# STM32F103RCT6MinSys.net
KiCad netlist of a schematic drawn in Altium Designer
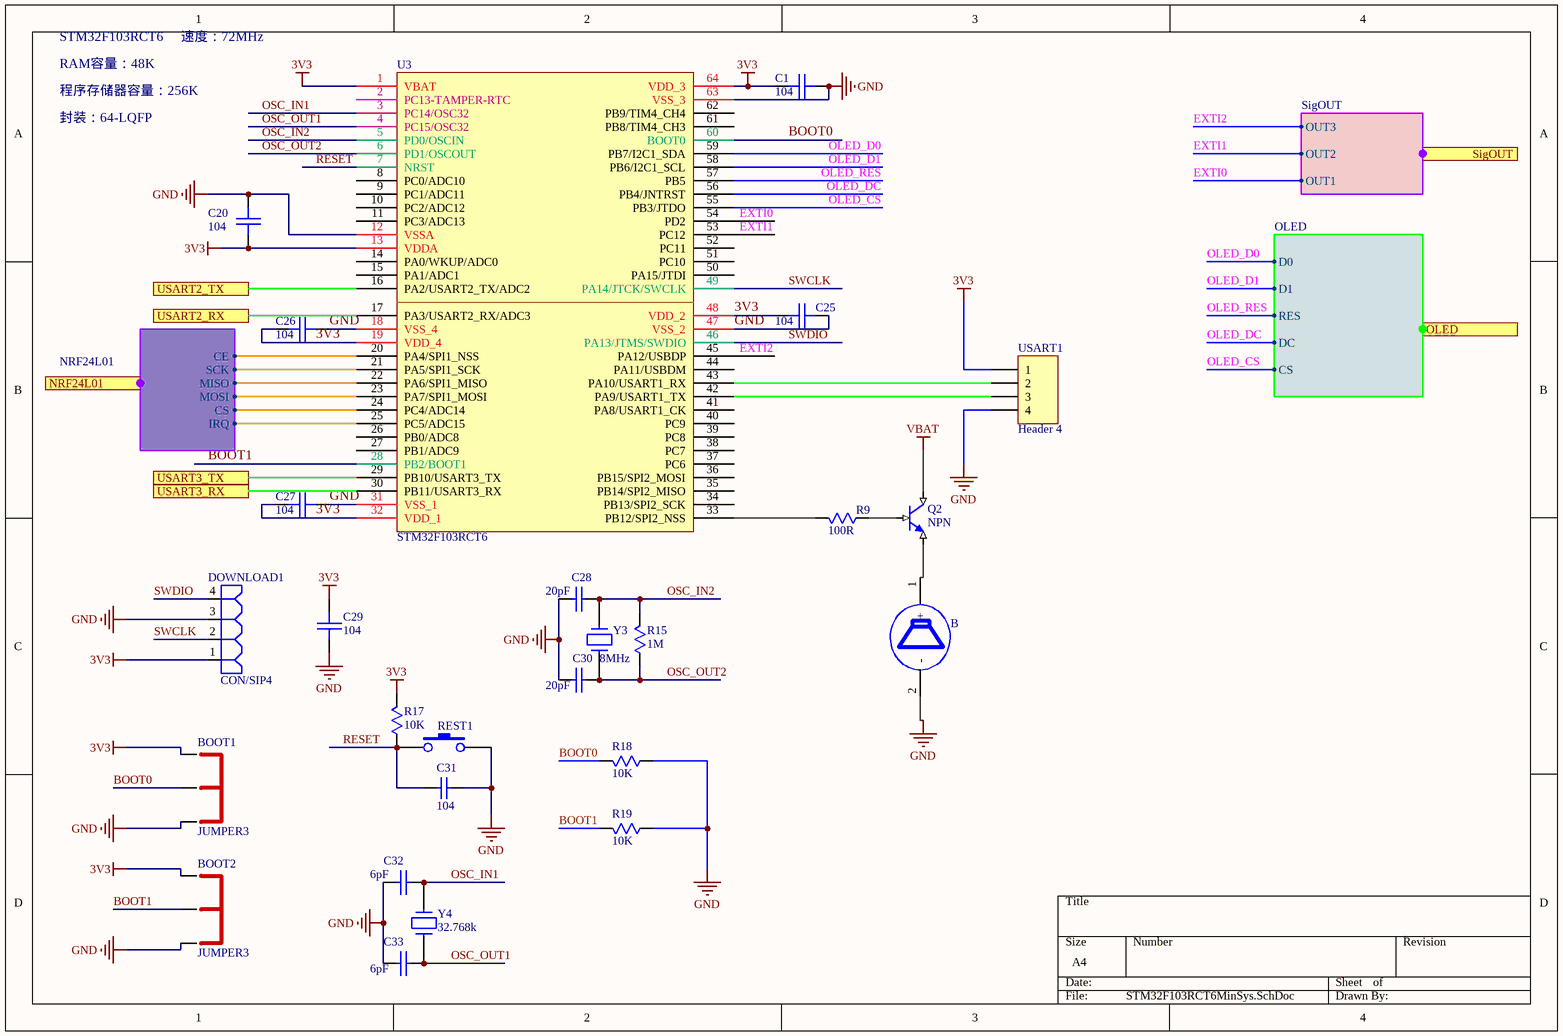
[diagram p0: STM32F103RCT6MinSys.SchDoc]

(export (version "E")
  (design (tool "Eeschema 10.0.6"))
  (components
    (comp (ref "B") (value "BEEP") (footprint "BEEP") (libsource (lib "常用原件库") (part "蜂鸣器")))
    (comp (ref "BOOT1")
      (value "JUMPER3")
      (footprint "Jumper3")
      (description "Jumper")
      (libsource (lib "LQ_Integrated_Library") (part "JUMPER3"))
    )
    (comp (ref "BOOT2")
      (value "JUMPER3")
      (footprint "Jumper3")
      (description "Jumper")
      (libsource (lib "LQ_Integrated_Library") (part "JUMPER3"))
    )
    (comp (ref "C1") (value "104") (footprint "C0603") (libsource (lib "YT1_SCH_99SE") (part "CAP")))
    (comp (ref "C20") (value "104") (footprint "C0603") (libsource (lib "YT1_SCH_99SE") (part "CAP")))
    (comp (ref "C25") (value "104") (footprint "C0603") (libsource (lib "YT1_SCH_99SE") (part "CAP")))
    (comp (ref "C26") (value "104") (footprint "C0603") (libsource (lib "YT1_SCH_99SE") (part "CAP")))
    (comp (ref "C27") (value "104") (footprint "C0603") (libsource (lib "YT1_SCH_99SE") (part "CAP")))
    (comp (ref "C28")
      (value "20pF")
      (footprint "LC-0603_C")
      (description "CAP CHIP 20P 50V(+-5% C0G 0603)")
      (libsource (lib "Miscellaneous Devices") (part "CAP"))
    )
    (comp (ref "C29") (value "104") (footprint "C0603") (libsource (lib "YT1_SCH_99SE") (part "CAP")))
    (comp (ref "C30")
      (value "20pF")
      (footprint "LC-0603_C")
      (description "CAP CHIP 20P 50V(+-5% C0G 0603)")
      (libsource (lib "Miscellaneous Devices") (part "CAP"))
    )
    (comp (ref "C31")
      (value "104")
      (footprint "LC-0603_C")
      (description "GRM39 X7R102K50PT")
      (fields (field (name "PUBLISHER") "Altium Limited"))
      (libsource (lib "") (part "CAP_1"))
    )
    (comp (ref "C32")
      (value "6pF")
      (footprint "LC-0603_C")
      (description "CAP CHIP 20P 50V(+-5% C0G 0603)")
      (libsource (lib "Miscellaneous Devices") (part "CAP"))
    )
    (comp (ref "C33")
      (value "6pF")
      (footprint "LC-0603_C")
      (description "CAP CHIP 20P 50V(+-5% C0G 0603)")
      (libsource (lib "Miscellaneous Devices") (part "CAP"))
    )
    (comp (ref "DOWNLOAD1")
      (value "CON/SIP4")
      (footprint "HDR1X4")
      (libsource (lib "LQ_Integrated_Library") (part "CON/SIP4"))
    )
    (comp (ref "Q2")
      (value "NPN")
      (footprint "SOT23-3")
      (description "triode")
      (libsource (lib "LQ_Integrated_Library") (part "NPN"))
    )
    (comp (ref "R9") (value "100R") (footprint "R0603") (libsource (lib "YT1_SCH_99SE") (part "RES")))
    (comp (ref "R15") (value "1M") (footprint "LC-0603_R") (libsource (lib "YT1_SCH_99SE") (part "RES")))
    (comp (ref "R17") (value "10K") (footprint "R0603") (libsource (lib "YT1_SCH_99SE") (part "RES")))
    (comp (ref "R18") (value "10K") (footprint "R0603") (libsource (lib "YT1_SCH_99SE") (part "RES")))
    (comp (ref "R19") (value "10K") (footprint "R0603") (libsource (lib "YT1_SCH_99SE") (part "RES")))
    (comp (ref "REST1") (value "~") (footprint "KEY-K2") (libsource (lib "*") (part "SW-PB")))
    (comp (ref "U3")
      (value "STM32F103RCT6")
      (footprint "LC-LQFP-64_10x10x05P")
      (libsource (lib "YT1_SCH_99SE") (part "STM32F103RBT6"))
    )
    (comp (ref "USART1")
      (value "Header 4")
      (footprint "HDR1X4")
      (description "Header, 4-Pin")
      (fields (field (name "PUBLISHER") "Altium Limited"))
      (libsource (lib "Miscellaneous Connectors") (part "Header 4"))
    )
    (comp (ref "Y3")
      (value "8MHz")
      (footprint "XTAL-49/S_N")
      (description "Crystal 8MHz PLUG")
      (libsource (lib "*") (part "CRYSTAL"))
    )
    (comp (ref "Y4")
      (value "32.768k")
      (footprint "XTAL_2X6 卧式")
      (description "Crystal 8MHz PLUG")
      (libsource (lib "*") (part "CRYSTAL"))
    )
  )
  (nets
    (net (code "4") (name "/BOOT0") (class "Default")
      (node (ref "BOOT1") (pin "2") (pinfunction "2_2") (pintype "passive"))
      (node (ref "R18") (pin "2") (pinfunction "2_2") (pintype "passive"))
      (node (ref "U3") (pin "60") (pinfunction "BOOT0_60") (pintype "passive"))
    )
    (net (code "5") (name "/BOOT1") (class "Default")
      (node (ref "BOOT2") (pin "2") (pinfunction "2_2") (pintype "passive"))
      (node (ref "R19") (pin "2") (pinfunction "2_2") (pintype "passive"))
      (node (ref "U3") (pin "28") (pinfunction "PB2/BOOT1_28") (pintype "passive"))
    )
    (net (code "6") (name "/CE") (class "Default")
      (node (ref "U3") (pin "20") (pinfunction "PA4/SPI1_NSS_20") (pintype "passive"))
    )
    (net (code "7") (name "/EXTI0") (class "Default")
      (node (ref "U3") (pin "54") (pinfunction "PD2_54") (pintype "passive"))
    )
    (net (code "8") (name "/EXTI1") (class "Default")
      (node (ref "U3") (pin "53") (pinfunction "PC12_53") (pintype "passive"))
    )
    (net (code "9") (name "/EXTI2") (class "Default")
      (node (ref "U3") (pin "45") (pinfunction "PA12/USBDP_45") (pintype "passive"))
    )
    (net (code "10") (name "/IRQ") (class "Default")
      (node (ref "U3") (pin "25") (pinfunction "PC5/ADC15_25") (pintype "passive"))
    )
    (net (code "11") (name "/MISO") (class "Default")
      (node (ref "U3") (pin "22") (pinfunction "PA6/SPI1_MISO_22") (pintype "passive"))
    )
    (net (code "12") (name "/MOSI") (class "Default")
      (node (ref "U3") (pin "23") (pinfunction "PA7/SPI1_MOSI_23") (pintype "passive"))
    )
    (net (code "13") (name "/OLED_CS") (class "Default")
      (node (ref "U3") (pin "55") (pinfunction "PB3/JTDO_55") (pintype "passive"))
    )
    (net (code "14") (name "/OLED_D0") (class "Default")
      (node (ref "U3") (pin "59") (pinfunction "PB7/I2C1_SDA_59") (pintype "passive"))
    )
    (net (code "15") (name "/OLED_D1") (class "Default")
      (node (ref "U3") (pin "58") (pinfunction "PB6/I2C1_SCL_58") (pintype "passive"))
    )
    (net (code "16") (name "/OLED_DC") (class "Default")
      (node (ref "U3") (pin "56") (pinfunction "PB4/JNTRST_56") (pintype "passive"))
    )
    (net (code "17") (name "/OLED_RES") (class "Default")
      (node (ref "U3") (pin "57") (pinfunction "PB5_57") (pintype "passive"))
    )
    (net (code "18") (name "/OSC_IN1") (class "Default")
      (node (ref "C32") (pin "2") (pinfunction "2_2") (pintype "passive"))
      (node (ref "U3") (pin "3") (pinfunction "PC14/OSC32_3") (pintype "passive"))
      (node (ref "Y4") (pin "2") (pinfunction "2_2") (pintype "passive"))
    )
    (net (code "19") (name "/OSC_IN2") (class "Default")
      (node (ref "C28") (pin "2") (pinfunction "2_2") (pintype "passive"))
      (node (ref "R15") (pin "2") (pinfunction "2_2") (pintype "passive"))
      (node (ref "U3") (pin "5") (pinfunction "PD0/OSCIN_5") (pintype "passive"))
      (node (ref "Y3") (pin "1") (pinfunction "1_1") (pintype "passive"))
    )
    (net (code "20") (name "/OSC_OUT1") (class "Default")
      (node (ref "C33") (pin "2") (pinfunction "2_2") (pintype "passive"))
      (node (ref "U3") (pin "4") (pinfunction "PC15/OSC32_4") (pintype "passive"))
      (node (ref "Y4") (pin "1") (pinfunction "1_1") (pintype "passive"))
    )
    (net (code "21") (name "/OSC_OUT2") (class "Default")
      (node (ref "C30") (pin "2") (pinfunction "2_2") (pintype "passive"))
      (node (ref "R15") (pin "1") (pinfunction "1_1") (pintype "passive"))
      (node (ref "U3") (pin "6") (pinfunction "PD1/OSCOUT_6") (pintype "passive"))
      (node (ref "Y3") (pin "2") (pinfunction "2_2") (pintype "passive"))
    )
    (net (code "22") (name "/RESET") (class "Default")
      (node (ref "C31") (pin "2") (pinfunction "2_2") (pintype "passive"))
      (node (ref "R17") (pin "1") (pinfunction "1_1") (pintype "passive"))
      (node (ref "REST1") (pin "1") (pinfunction "1_1") (pintype "passive"))
      (node (ref "U3") (pin "7") (pinfunction "NRST_7") (pintype "passive"))
    )
    (net (code "23") (name "/SCK") (class "Default")
      (node (ref "U3") (pin "21") (pinfunction "PA5/SPI1_SCK_21") (pintype "passive"))
    )
    (net (code "24") (name "/SWCLK") (class "Default")
      (node (ref "DOWNLOAD1") (pin "2") (pintype "passive"))
      (node (ref "U3") (pin "49") (pinfunction "PA14/JTCK/SWCLK_49") (pintype "passive"))
    )
    (net (code "25") (name "/SWDIO") (class "Default")
      (node (ref "DOWNLOAD1") (pin "4") (pintype "passive"))
      (node (ref "U3") (pin "46") (pinfunction "PA13/JTMS/SWDIO_46") (pintype "passive"))
    )
    (net (code "26") (name "/USART2_RX") (class "Default")
      (node (ref "U3") (pin "17") (pinfunction "PA3/USART2_RX/ADC3_17") (pintype "passive"))
    )
    (net (code "27") (name "/USART2_TX") (class "Default")
      (node (ref "U3") (pin "16") (pinfunction "PA2/USART2_TX/ADC2_16") (pintype "passive"))
    )
    (net (code "28") (name "/USART3_RX") (class "Default")
      (node (ref "U3") (pin "30") (pinfunction "PB11/USART3_RX_30") (pintype "passive"))
    )
    (net (code "29") (name "/USART3_TX") (class "Default")
      (node (ref "U3") (pin "29") (pinfunction "PB10/USART3_TX_29") (pintype "passive"))
    )
    (net (code "33") (name "3V3") (class "Default")
      (node (ref "BOOT1") (pin "1") (pinfunction "1_1") (pintype "passive"))
      (node (ref "BOOT2") (pin "1") (pinfunction "1_1") (pintype "passive"))
      (node (ref "C1") (pin "1") (pinfunction "1_1") (pintype "passive"))
      (node (ref "C20") (pin "2") (pinfunction "2_2") (pintype "passive"))
      (node (ref "C25") (pin "1") (pinfunction "1_1") (pintype "passive"))
      (node (ref "C26") (pin "1") (pinfunction "1_1") (pintype "passive"))
      (node (ref "C27") (pin "1") (pinfunction "1_1") (pintype "passive"))
      (node (ref "C29") (pin "1") (pinfunction "1_1") (pintype "passive"))
      (node (ref "DOWNLOAD1") (pin "1") (pintype "passive"))
      (node (ref "R17") (pin "2") (pinfunction "2_2") (pintype "passive"))
      (node (ref "U3") (pin "1") (pinfunction "VBAT_1") (pintype "passive"))
      (node (ref "U3") (pin "13") (pinfunction "VDDA_13") (pintype "passive"))
      (node (ref "U3") (pin "19") (pinfunction "VDD_4_19") (pintype "passive"))
      (node (ref "U3") (pin "32") (pinfunction "VDD_1_32") (pintype "passive"))
      (node (ref "U3") (pin "48") (pinfunction "VDD_2_48") (pintype "passive"))
      (node (ref "U3") (pin "64") (pinfunction "VDD_3_64") (pintype "passive"))
      (node (ref "USART1") (pin "1") (pinfunction "1_1") (pintype "passive"))
    )
    (net (code "34") (name "GND") (class "Default")
      (node (ref "B") (pin "2") (pinfunction "-_2") (pintype "passive"))
      (node (ref "BOOT1") (pin "3") (pinfunction "3_3") (pintype "passive"))
      (node (ref "BOOT2") (pin "3") (pinfunction "3_3") (pintype "passive"))
      (node (ref "C1") (pin "2") (pinfunction "2_2") (pintype "passive"))
      (node (ref "C20") (pin "1") (pinfunction "1_1") (pintype "passive"))
      (node (ref "C25") (pin "2") (pinfunction "2_2") (pintype "passive"))
      (node (ref "C26") (pin "2") (pinfunction "2_2") (pintype "passive"))
      (node (ref "C27") (pin "2") (pinfunction "2_2") (pintype "passive"))
      (node (ref "C28") (pin "1") (pinfunction "1_1") (pintype "passive"))
      (node (ref "C29") (pin "2") (pinfunction "2_2") (pintype "passive"))
      (node (ref "C30") (pin "1") (pinfunction "1_1") (pintype "passive"))
      (node (ref "C31") (pin "1") (pinfunction "1_1") (pintype "passive"))
      (node (ref "C32") (pin "1") (pinfunction "1_1") (pintype "passive"))
      (node (ref "C33") (pin "1") (pinfunction "1_1") (pintype "passive"))
      (node (ref "DOWNLOAD1") (pin "3") (pintype "passive"))
      (node (ref "R18") (pin "1") (pinfunction "1_1") (pintype "passive"))
      (node (ref "R19") (pin "1") (pinfunction "1_1") (pintype "passive"))
      (node (ref "REST1") (pin "2") (pinfunction "2_2") (pintype "passive"))
      (node (ref "U3") (pin "12") (pinfunction "VSSA_12") (pintype "passive"))
      (node (ref "U3") (pin "18") (pinfunction "VSS_4_18") (pintype "passive"))
      (node (ref "U3") (pin "31") (pinfunction "VSS_1_31") (pintype "passive"))
      (node (ref "U3") (pin "47") (pinfunction "VSS_2_47") (pintype "passive"))
      (node (ref "U3") (pin "63") (pinfunction "VSS_3_63") (pintype "passive"))
      (node (ref "USART1") (pin "4") (pinfunction "4_4") (pintype "passive"))
    )
    (net (code "35") (name "Net-(B-+)") (class "Default")
      (node (ref "B") (pin "1") (pinfunction "+_1") (pintype "passive"))
      (node (ref "Q2") (pin "1") (pinfunction "E_1") (pintype "input"))
    )
    (net (code "36") (name "Net-(Q2-B)") (class "Default")
      (node (ref "Q2") (pin "2") (pinfunction "B_2") (pintype "input"))
      (node (ref "R9") (pin "1") (pinfunction "1_1") (pintype "passive"))
    )
    (net (code "37") (name "Net-(U3-PA9{slash}USART1_TX)") (class "Default")
      (node (ref "U3") (pin "42") (pinfunction "PA9/USART1_TX_42") (pintype "passive"))
      (node (ref "USART1") (pin "3") (pinfunction "3_3") (pintype "passive"))
    )
    (net (code "38") (name "Net-(U3-PA10{slash}USART1_RX)") (class "Default")
      (node (ref "U3") (pin "43") (pinfunction "PA10/USART1_RX_43") (pintype "passive"))
      (node (ref "USART1") (pin "2") (pinfunction "2_2") (pintype "passive"))
    )
    (net (code "39") (name "Net-(U3-PB12{slash}SPI2_NSS)") (class "Default")
      (node (ref "R9") (pin "2") (pinfunction "2_2") (pintype "passive"))
      (node (ref "U3") (pin "33") (pinfunction "PB12/SPI2_NSS_33") (pintype "passive"))
    )
    (net (code "40") (name "VBAT") (class "Default")
      (node (ref "Q2") (pin "3") (pinfunction "C_3") (pintype "input"))
    )
    (net (code "41") (name "unconnected-(U3-PA0{slash}WKUP{slash}ADC0-Pad14)") (class "Default")
      (node (ref "U3") (pin "14") (pinfunction "PA0/WKUP/ADC0_14") (pintype "passive"))
    )
    (net (code "42") (name "unconnected-(U3-PA1{slash}ADC1-Pad15)") (class "Default")
      (node (ref "U3") (pin "15") (pinfunction "PA1/ADC1_15") (pintype "passive"))
    )
    (net (code "43") (name "unconnected-(U3-PA8{slash}USART1_CK-Pad41)") (class "Default")
      (node (ref "U3") (pin "41") (pinfunction "PA8/USART1_CK_41") (pintype "passive"))
    )
    (net (code "44") (name "unconnected-(U3-PA11{slash}USBDM-Pad44)") (class "Default")
      (node (ref "U3") (pin "44") (pinfunction "PA11/USBDM_44") (pintype "passive"))
    )
    (net (code "45") (name "unconnected-(U3-PA15{slash}JTDI-Pad50)") (class "Default")
      (node (ref "U3") (pin "50") (pinfunction "PA15/JTDI_50") (pintype "passive"))
    )
    (net (code "46") (name "unconnected-(U3-PB0{slash}ADC8-Pad26)") (class "Default")
      (node (ref "U3") (pin "26") (pinfunction "PB0/ADC8_26") (pintype "passive"))
    )
    (net (code "47") (name "unconnected-(U3-PB1{slash}ADC9-Pad27)") (class "Default")
      (node (ref "U3") (pin "27") (pinfunction "PB1/ADC9_27") (pintype "passive"))
    )
    (net (code "48") (name "unconnected-(U3-PB8{slash}TIM4_CH3-Pad61)") (class "Default")
      (node (ref "U3") (pin "61") (pinfunction "PB8/TIM4_CH3_61") (pintype "passive"))
    )
    (net (code "49") (name "unconnected-(U3-PB9{slash}TIM4_CH4-Pad62)") (class "Default")
      (node (ref "U3") (pin "62") (pinfunction "PB9/TIM4_CH4_62") (pintype "passive"))
    )
    (net (code "50") (name "unconnected-(U3-PB13{slash}SPI2_SCK-Pad34)") (class "Default")
      (node (ref "U3") (pin "34") (pinfunction "PB13/SPI2_SCK_34") (pintype "passive"))
    )
    (net (code "51") (name "unconnected-(U3-PB14{slash}SPI2_MISO-Pad35)") (class "Default")
      (node (ref "U3") (pin "35") (pinfunction "PB14/SPI2_MISO_35") (pintype "passive"))
    )
    (net (code "52") (name "unconnected-(U3-PB15{slash}SPI2_MOSI-Pad36)") (class "Default")
      (node (ref "U3") (pin "36") (pinfunction "PB15/SPI2_MOSI_36") (pintype "passive"))
    )
    (net (code "53") (name "unconnected-(U3-PC0{slash}ADC10-Pad8)") (class "Default")
      (node (ref "U3") (pin "8") (pinfunction "PC0/ADC10_8") (pintype "passive"))
    )
    (net (code "54") (name "unconnected-(U3-PC1{slash}ADC11-Pad9)") (class "Default")
      (node (ref "U3") (pin "9") (pinfunction "PC1/ADC11_9") (pintype "passive"))
    )
    (net (code "55") (name "unconnected-(U3-PC2{slash}ADC12-Pad10)") (class "Default")
      (node (ref "U3") (pin "10") (pinfunction "PC2/ADC12_10") (pintype "passive"))
    )
    (net (code "56") (name "unconnected-(U3-PC3{slash}ADC13-Pad11)") (class "Default")
      (node (ref "U3") (pin "11") (pinfunction "PC3/ADC13_11") (pintype "passive"))
    )
    (net (code "57") (name "unconnected-(U3-PC4{slash}ADC14-Pad24)") (class "Default")
      (node (ref "U3") (pin "24") (pinfunction "PC4/ADC14_24") (pintype "passive"))
    )
    (net (code "58") (name "unconnected-(U3-PC6-Pad37)") (class "Default")
      (node (ref "U3") (pin "37") (pinfunction "PC6_37") (pintype "passive"))
    )
    (net (code "59") (name "unconnected-(U3-PC7-Pad38)") (class "Default")
      (node (ref "U3") (pin "38") (pinfunction "PC7_38") (pintype "passive"))
    )
    (net (code "60") (name "unconnected-(U3-PC8-Pad39)") (class "Default")
      (node (ref "U3") (pin "39") (pinfunction "PC8_39") (pintype "passive"))
    )
    (net (code "61") (name "unconnected-(U3-PC9-Pad40)") (class "Default")
      (node (ref "U3") (pin "40") (pinfunction "PC9_40") (pintype "passive"))
    )
    (net (code "62") (name "unconnected-(U3-PC10-Pad51)") (class "Default")
      (node (ref "U3") (pin "51") (pinfunction "PC10_51") (pintype "passive"))
    )
    (net (code "63") (name "unconnected-(U3-PC11-Pad52)") (class "Default")
      (node (ref "U3") (pin "52") (pinfunction "PC11_52") (pintype "passive"))
    )
    (net (code "64") (name "unconnected-(U3-PC13-TAMPER-RTC-Pad2)") (class "Default")
      (node (ref "U3") (pin "2") (pinfunction "PC13-TAMPER-RTC_2") (pintype "passive"))
    )
  )
)
